# wheatstone_bridge.net
KiCad netlist of a schematic drawn in EAGLE
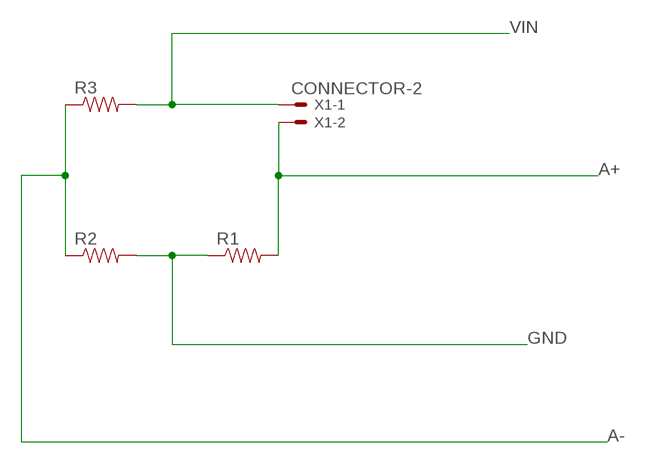
[diagram p0: schematic, sheet 1]

(export (version "E")
  (design (tool "Eeschema 10.0.6"))
  (components
    (comp (ref "R1")
      (value "RESISTORAXIAL-0.3")
      (footprint "eagle-import:AXIAL-0.3")
      (libsource (lib "eagle-import") (part "RESISTORAXIAL-0.3"))
    )
    (comp (ref "R2")
      (value "RESISTORAXIAL-0.3")
      (footprint "eagle-import:AXIAL-0.3")
      (libsource (lib "eagle-import") (part "RESISTORAXIAL-0.3"))
    )
    (comp (ref "R3")
      (value "RESISTORAXIAL-0.3")
      (footprint "eagle-import:AXIAL-0.3")
      (libsource (lib "eagle-import") (part "RESISTORAXIAL-0.3"))
    )
    (comp (ref "X1")
      (value "CONNECTOR-2")
      (footprint "eagle-import:MINIFIT_5566-2")
      (libsource (lib "eagle-import") (part "CONNECTOR-2"))
    )
  )
  (nets
    (net (code "1") (name "/A+") (class "Default")
      (node (ref "R1") (pin "P$2") (pinfunction "2_P$2") (pintype "passive"))
      (node (ref "X1") (pin "2") (pinfunction "S_2") (pintype "passive"))
    )
    (net (code "2") (name "/A-") (class "Default")
      (node (ref "R2") (pin "P$1") (pinfunction "1_P$1") (pintype "passive"))
      (node (ref "R3") (pin "P$1") (pinfunction "1_P$1") (pintype "passive"))
    )
    (net (code "3") (name "/GND") (class "Default")
      (node (ref "R1") (pin "P$1") (pinfunction "1_P$1") (pintype "passive"))
      (node (ref "R2") (pin "P$2") (pinfunction "2_P$2") (pintype "passive"))
    )
    (net (code "4") (name "/VIN") (class "Default")
      (node (ref "R3") (pin "P$2") (pinfunction "2_P$2") (pintype "passive"))
      (node (ref "X1") (pin "1") (pinfunction "S_1") (pintype "passive"))
    )
  )
)
